# AT_Guard_Simple_RTC.net
KiCad netlist of a schematic drawn in Altium Designer
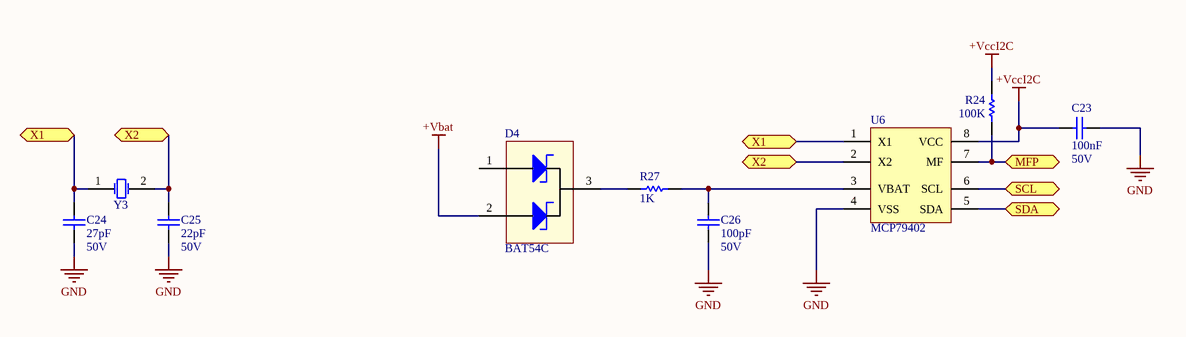
[diagram p0: AT Guard Simple RTC.SchDoc]

(export (version "E")
  (design (tool "Eeschema 10.0.6"))
  (components
    (comp (ref "C23")
      (value "100nF")
      (footprint "3-0603_L")
      (description "Capacitor")
      (fields
        (field (name "VOLTAGE") "50V")
        (field (name "Comment") "Cap")
        (field (name "PUBLISHER") "Altium Limited")
      )
      (libsource (lib "Erdem_05112012") (part "Cap"))
    )
    (comp (ref "C24")
      (value "27pF")
      (footprint "3-0603_L")
      (description "Capacitor")
      (fields
        (field (name "VOLTAGE") "50V")
        (field (name "Comment") "Cap")
        (field (name "PUBLISHER") "Altium Limited")
      )
      (libsource (lib "Erdem_05112012") (part "Cap"))
    )
    (comp (ref "C25")
      (value "22pF")
      (footprint "3-0603_L")
      (description "Capacitor")
      (fields
        (field (name "VOLTAGE") "50V")
        (field (name "Comment") "Cap")
        (field (name "PUBLISHER") "Altium Limited")
      )
      (libsource (lib "Erdem_05112012") (part "Cap"))
    )
    (comp (ref "C26")
      (value "100pF")
      (footprint "3-0603_L")
      (description "Capacitor")
      (fields
        (field (name "VOLTAGE") "50V")
        (field (name "Comment") "Cap")
        (field (name "PUBLISHER") "Altium Limited")
      )
      (libsource (lib "Erdem_05112012") (part "Cap"))
    )
    (comp (ref "D4")
      (value "BAT54C")
      (footprint "SOT23_N")
      (description "2x200 mA Shottky Rectifier")
      (fields (field (name "PUBLISHER") "Altium Limited"))
      (libsource (lib "Erdem_05112012") (part "BAT54C"))
    )
    (comp (ref "R24")
      (value "100K")
      (footprint "3-0603_L")
      (description "Resistor")
      (fields (field (name "Comment") "Res1") (field (name "PUBLISHER") "Altium Limited"))
      (libsource (lib "Erdem_05112012") (part "Res1"))
    )
    (comp (ref "R27")
      (value "1K")
      (footprint "3-0603_L")
      (description "Resistor")
      (fields (field (name "Comment") "Res1") (field (name "PUBLISHER") "Altium Limited"))
      (libsource (lib "Erdem_05112012") (part "Res1"))
    )
    (comp (ref "U6")
      (value "MCP79402")
      (footprint "TSSOP-ST8_M")
      (description "MCP79402 RTC,I2C")
      (fields (field (name "PUBLISHER") "Altium Limited"))
      (libsource (lib "Erdem_05112012") (part "MCP79402"))
    )
    (comp (ref "Y3")
      (value "XTAL_SMT")
      (footprint "32768 SMT 2.1x6.2mm Crystal")
      (description "Crystal Oscillator")
      (fields (field (name "PUBLISHER") "Altium Limited"))
      (libsource (lib "Erdem_05112012") (part "XTAL_SMT"))
    )
  )
  (nets
    (net (code "1") (name "+Vbat") (class "Default")
      (node (ref "D4") (pin "2") (pinfunction "K2_2") (pintype "passive"))
    )
    (net (code "2") (name "+VccI2C") (class "Default")
      (node (ref "C23") (pin "1") (pinfunction "1_1") (pintype "passive"))
      (node (ref "R24") (pin "1") (pinfunction "1_1") (pintype "passive"))
      (node (ref "U6") (pin "8") (pinfunction "VCC_8") (pintype "power_in"))
    )
    (net (code "3") (name "/MFP") (class "Default")
      (node (ref "R24") (pin "2") (pinfunction "2_2") (pintype "passive"))
      (node (ref "U6") (pin "7") (pinfunction "MF_7") (pintype "passive"))
    )
    (net (code "4") (name "/SCL") (class "Default")
      (node (ref "U6") (pin "6") (pinfunction "SCL_6") (pintype "passive"))
    )
    (net (code "5") (name "/SDA") (class "Default")
      (node (ref "U6") (pin "5") (pinfunction "SDA_5") (pintype "passive"))
    )
    (net (code "6") (name "/X1") (class "Default")
      (node (ref "C24") (pin "2") (pinfunction "2_2") (pintype "passive"))
      (node (ref "U6") (pin "1") (pinfunction "X1_1") (pintype "passive"))
      (node (ref "Y3") (pin "1") (pinfunction "OSC1_1") (pintype "passive"))
    )
    (net (code "7") (name "/X2") (class "Default")
      (node (ref "C25") (pin "2") (pinfunction "2_2") (pintype "passive"))
      (node (ref "U6") (pin "2") (pinfunction "X2_2") (pintype "passive"))
      (node (ref "Y3") (pin "2") (pinfunction "OSC2_2") (pintype "passive"))
    )
    (net (code "8") (name "GND") (class "Default")
      (node (ref "C23") (pin "2") (pinfunction "2_2") (pintype "passive"))
      (node (ref "C24") (pin "1") (pinfunction "1_1") (pintype "passive"))
      (node (ref "C25") (pin "1") (pinfunction "1_1") (pintype "passive"))
      (node (ref "C26") (pin "1") (pinfunction "1_1") (pintype "passive"))
      (node (ref "U6") (pin "4") (pinfunction "VSS_4") (pintype "power_in"))
    )
    (net (code "9") (name "Net-(D4-A)") (class "Default")
      (node (ref "D4") (pin "3") (pinfunction "A_3") (pintype "passive"))
      (node (ref "R27") (pin "1") (pinfunction "1_1") (pintype "passive"))
    )
    (net (code "10") (name "Net-(U6-VBAT)") (class "Default")
      (node (ref "C26") (pin "2") (pinfunction "2_2") (pintype "passive"))
      (node (ref "R27") (pin "2") (pinfunction "2_2") (pintype "passive"))
      (node (ref "U6") (pin "3") (pinfunction "VBAT_3") (pintype "passive"))
    )
    (net (code "11") (name "unconnected-(D4-K1-Pad1)") (class "Default")
      (node (ref "D4") (pin "1") (pinfunction "K1_1") (pintype "passive"))
    )
  )
)
